# Heaterboard.net
KiCad netlist of a schematic drawn in EAGLE
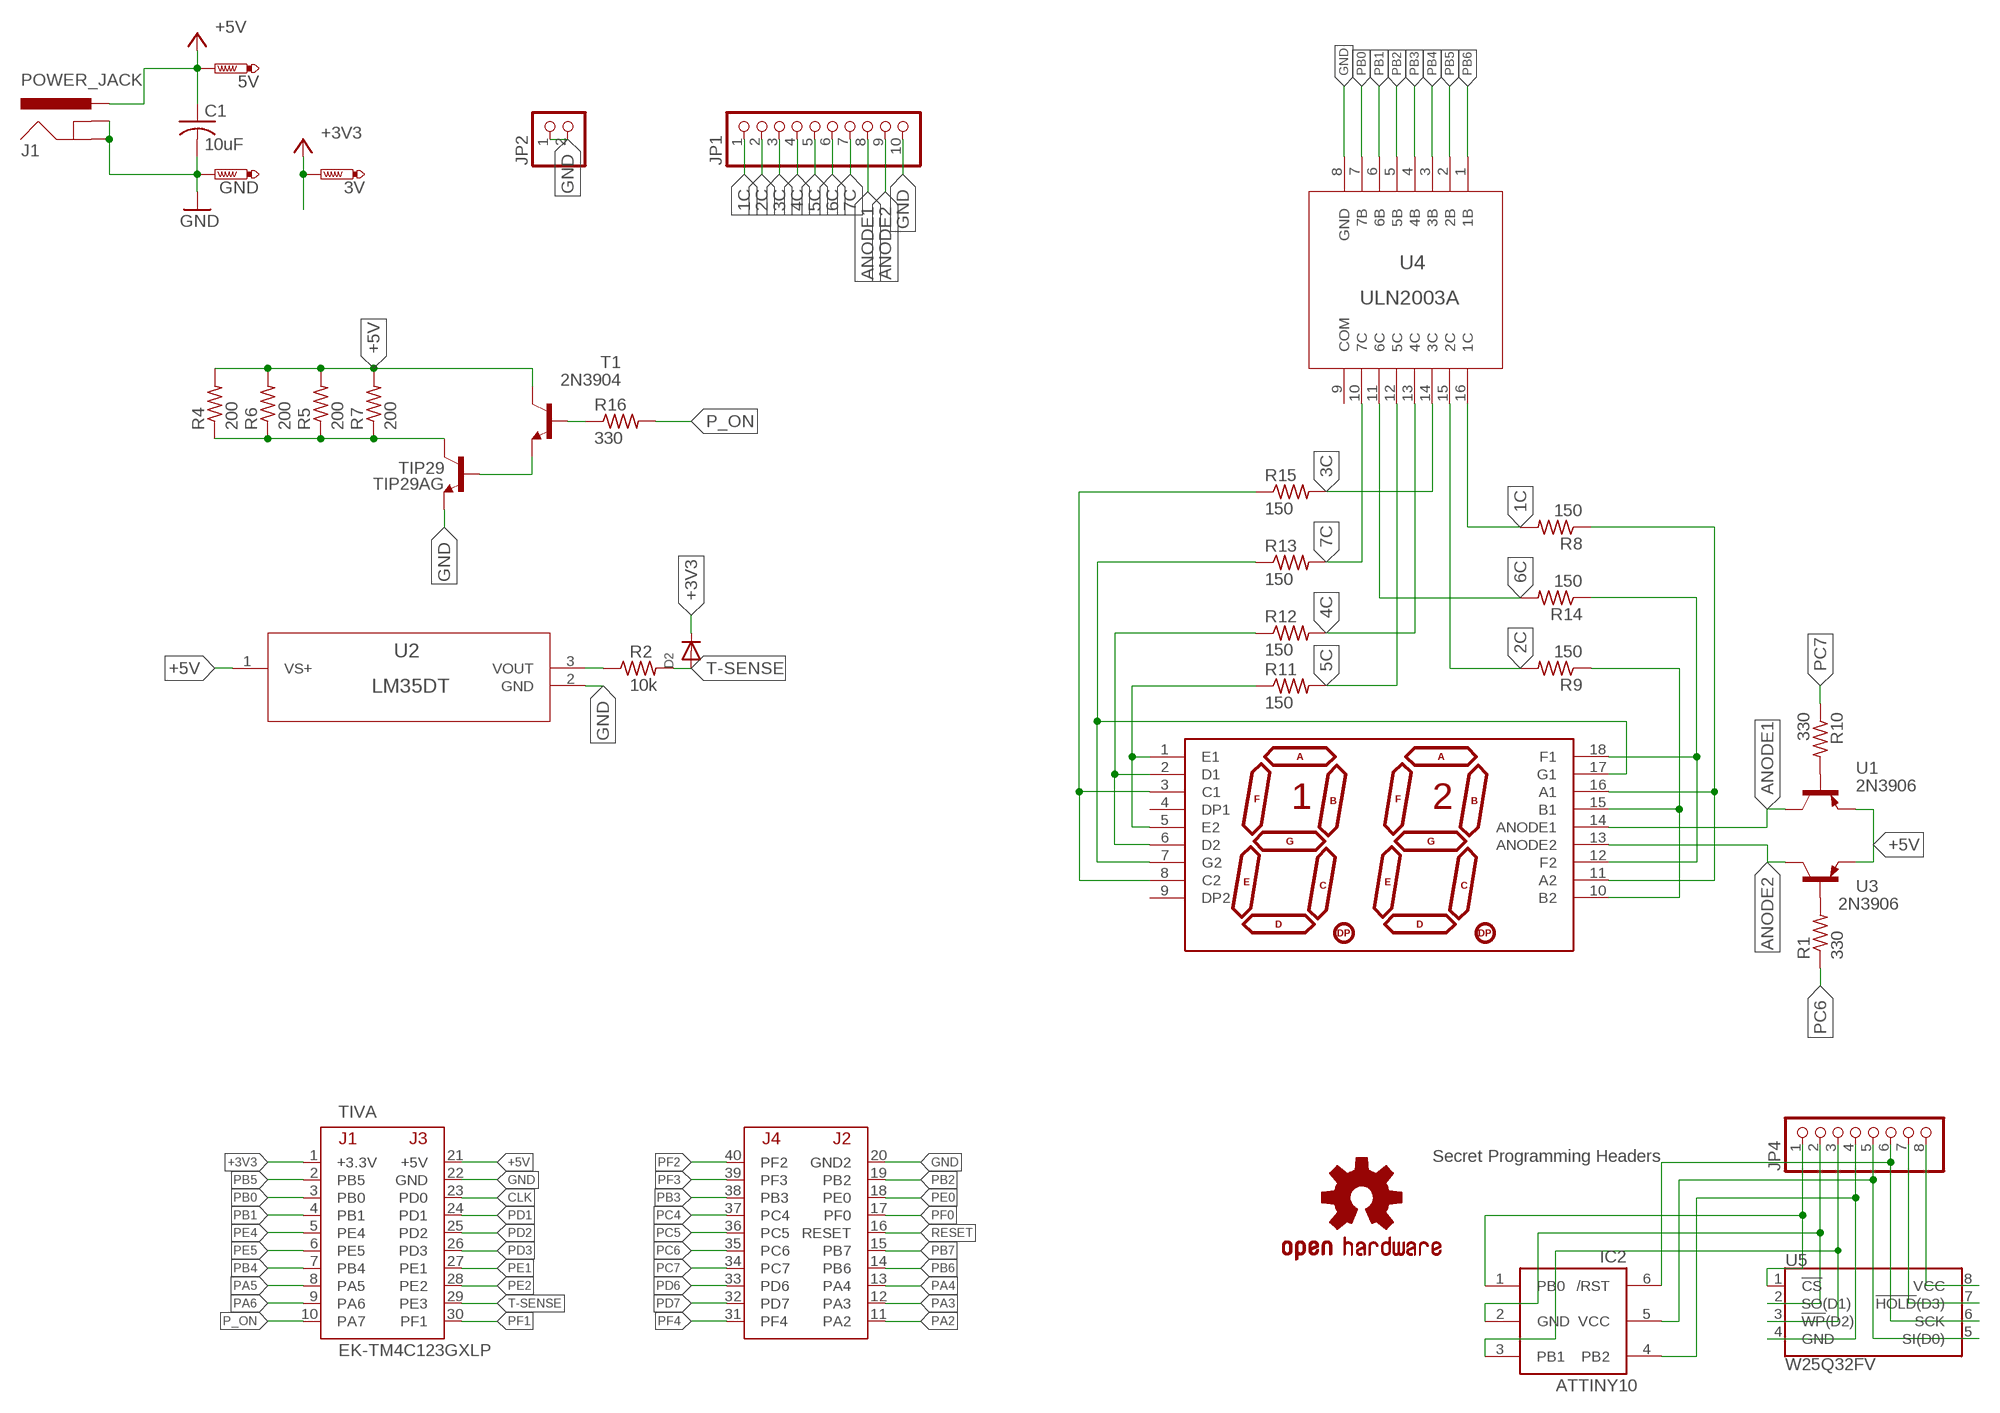
[diagram p0: schematic, sheet 1]

(export (version "E")
  (design (tool "Eeschema 10.0.6"))
  (components
    (comp (ref "3V")
      (value "PTR1PAD1-13")
      (footprint "eagle-import:P1-13")
      (libsource (lib "eagle-import") (part "PTR1PAD1-13"))
    )
    (comp (ref "5V")
      (value "PTR1PAD1-13")
      (footprint "eagle-import:P1-13")
      (libsource (lib "eagle-import") (part "PTR1PAD1-13"))
    )
    (comp (ref "7SEG")
      (value "NTE3074")
      (footprint "eagle-import:NTE3074")
      (libsource (lib "eagle-import") (part "NTE3074"))
    )
    (comp (ref "C1")
      (value "10uF")
      (footprint "eagle-import:C025-030X050")
      (libsource (lib "eagle-import") (part "C-US025-030X050"))
    )
    (comp (ref "D2")
      (value "DIODEDO-1N4148")
      (footprint "eagle-import:DO-1N4148")
      (libsource (lib "eagle-import") (part "DIODEDO-1N4148"))
    )
    (comp (ref "GND")
      (value "PTR1PAD1-13")
      (footprint "eagle-import:P1-13")
      (libsource (lib "eagle-import") (part "PTR1PAD1-13"))
    )
    (comp (ref "IC2")
      (value "ATTINY10")
      (footprint "eagle-import:SOT23-6")
      (libsource (lib "eagle-import") (part "ATTINY10"))
    )
    (comp (ref "J1")
      (value "POWER_JACK")
      (footprint "eagle-import:POWER_JACK_PTH")
      (libsource (lib "eagle-import") (part "POWER_JACK"))
    )
    (comp (ref "JP1")
      (value "PINHD-1X10/90")
      (footprint "eagle-import:1X10_90")
      (libsource (lib "eagle-import") (part "PINHD-1X10/90"))
    )
    (comp (ref "JP2")
      (value "PINHD-1X2")
      (footprint "eagle-import:1X02")
      (libsource (lib "eagle-import") (part "PINHD-1X2"))
    )
    (comp (ref "JP4")
      (value "PINHD-1X8")
      (footprint "eagle-import:1X08")
      (libsource (lib "eagle-import") (part "PINHD-1X8"))
    )
    (comp (ref "LOGO1")
      (value "OSHW-LOGOL")
      (footprint "eagle-import:OSHW-LOGO-L")
      (libsource (lib "eagle-import") (part "OSHW-LOGOL"))
    )
    (comp (ref "R1")
      (value "330")
      (footprint "eagle-import:0204_5")
      (libsource (lib "eagle-import") (part "R-US_0204/5"))
    )
    (comp (ref "R2")
      (value "10k")
      (footprint "eagle-import:0204_5")
      (libsource (lib "eagle-import") (part "R-US_0204/5"))
    )
    (comp (ref "R4")
      (value "200")
      (footprint "eagle-import:0207_10")
      (libsource (lib "eagle-import") (part "R-US_0207/10"))
    )
    (comp (ref "R5")
      (value "200")
      (footprint "eagle-import:0207_10")
      (libsource (lib "eagle-import") (part "R-US_0207/10"))
    )
    (comp (ref "R6")
      (value "200")
      (footprint "eagle-import:0207_10")
      (libsource (lib "eagle-import") (part "R-US_0207/10"))
    )
    (comp (ref "R7")
      (value "200")
      (footprint "eagle-import:0207_10")
      (libsource (lib "eagle-import") (part "R-US_0207/10"))
    )
    (comp (ref "R8")
      (value "150")
      (footprint "eagle-import:0204_5")
      (libsource (lib "eagle-import") (part "R-US_0204/5"))
    )
    (comp (ref "R9")
      (value "150")
      (footprint "eagle-import:0204_5")
      (libsource (lib "eagle-import") (part "R-US_0204/5"))
    )
    (comp (ref "R10")
      (value "330")
      (footprint "eagle-import:0204_5")
      (libsource (lib "eagle-import") (part "R-US_0204/5"))
    )
    (comp (ref "R11")
      (value "150")
      (footprint "eagle-import:0204_5")
      (libsource (lib "eagle-import") (part "R-US_0204/5"))
    )
    (comp (ref "R12")
      (value "150")
      (footprint "eagle-import:0204_5")
      (libsource (lib "eagle-import") (part "R-US_0204/5"))
    )
    (comp (ref "R13")
      (value "150")
      (footprint "eagle-import:0204_5")
      (libsource (lib "eagle-import") (part "R-US_0204/5"))
    )
    (comp (ref "R14")
      (value "150")
      (footprint "eagle-import:0204_5")
      (libsource (lib "eagle-import") (part "R-US_0204/5"))
    )
    (comp (ref "R15")
      (value "150")
      (footprint "eagle-import:0204_5")
      (libsource (lib "eagle-import") (part "R-US_0204/5"))
    )
    (comp (ref "R16")
      (value "330")
      (footprint "eagle-import:0204_5")
      (libsource (lib "eagle-import") (part "R-US_0204/5"))
    )
    (comp (ref "T1")
      (value "2N3904")
      (footprint "eagle-import:TO92")
      (libsource (lib "eagle-import") (part "2N3904"))
    )
    (comp (ref "TIP29")
      (value "TIP29AG")
      (footprint "eagle-import:TO220")
      (libsource (lib "eagle-import") (part "TIP29AG"))
    )
    (comp (ref "TIVA")
      (value "EK-TM4C123GXLP")
      (footprint "eagle-import:TM4C123LAUNCHPAD")
      (fields (field (name "MF") "Texas Instruments") (field (name "MP") "EK-TM4C123GXL"))
      (libsource (lib "eagle-import") (part "EK-TM4C123GXLP"))
    )
    (comp (ref "U1")
      (value "2N3906")
      (footprint "eagle-import:TO-92_2")
      (libsource (lib "eagle-import") (part "2N3906"))
    )
    (comp (ref "U2")
      (value "LM35DT")
      (footprint "eagle-import:TA03F")
      (libsource (lib "eagle-import") (part "LM35DT"))
    )
    (comp (ref "U3")
      (value "2N3906")
      (footprint "eagle-import:TO-92_2")
      (libsource (lib "eagle-import") (part "2N3906"))
    )
    (comp (ref "U4")
      (value "ULN2003A")
      (footprint "eagle-import:DIP-16")
      (libsource (lib "eagle-import") (part "ULN2003A"))
    )
    (comp (ref "U5")
      (value "W25Q32FV")
      (footprint "eagle-import:SOIC-8")
      (libsource (lib "eagle-import") (part "W25Q32FVSS"))
    )
  )
  (nets
    (net (code "1") (name "+3V3") (class "Default")
      (node (ref "3V") (pin "TP") (pinfunction "TP_TP") (pintype "input"))
      (node (ref "D2") (pin "C") (pinfunction "C_C") (pintype "passive"))
      (node (ref "TIVA") (pin "1") (pinfunction "+3.3V_1") (pintype "power_in"))
    )
    (net (code "2") (name "+5V") (class "Default")
      (node (ref "5V") (pin "TP") (pinfunction "TP_TP") (pintype "input"))
      (node (ref "C1") (pin "1") (pinfunction "1_1") (pintype "passive"))
      (node (ref "J1") (pin "PWR") (pinfunction "PWR_PWR") (pintype "bidirectional"))
      (node (ref "R4") (pin "2") (pinfunction "2_2") (pintype "passive"))
      (node (ref "R5") (pin "2") (pinfunction "2_2") (pintype "passive"))
      (node (ref "R6") (pin "2") (pinfunction "2_2") (pintype "passive"))
      (node (ref "R7") (pin "2") (pinfunction "2_2") (pintype "passive"))
      (node (ref "T1") (pin "1") (pinfunction "C_1") (pintype "passive"))
      (node (ref "TIVA") (pin "21") (pinfunction "+5V_21") (pintype "power_in"))
      (node (ref "U1") (pin "3") (pinfunction "E_3") (pintype "passive"))
      (node (ref "U2") (pin "1") (pinfunction "VS+_1") (pintype "input"))
      (node (ref "U3") (pin "3") (pinfunction "E_3") (pintype "passive"))
    )
    (net (code "3") (name "1C") (class "Default")
      (node (ref "JP1") (pin "1") (pinfunction "1_1") (pintype "passive"))
      (node (ref "R8") (pin "2") (pinfunction "2_2") (pintype "passive"))
      (node (ref "U4") (pin "16") (pinfunction "1C_16") (pintype "passive"))
    )
    (net (code "4") (name "2C") (class "Default")
      (node (ref "JP1") (pin "2") (pinfunction "2_2") (pintype "passive"))
      (node (ref "R9") (pin "2") (pinfunction "2_2") (pintype "passive"))
      (node (ref "U4") (pin "15") (pinfunction "2C_15") (pintype "passive"))
    )
    (net (code "5") (name "3C") (class "Default")
      (node (ref "JP1") (pin "3") (pinfunction "3_3") (pintype "passive"))
      (node (ref "R15") (pin "2") (pinfunction "2_2") (pintype "passive"))
      (node (ref "U4") (pin "14") (pinfunction "3C_14") (pintype "passive"))
    )
    (net (code "6") (name "4C") (class "Default")
      (node (ref "JP1") (pin "4") (pinfunction "4_4") (pintype "passive"))
      (node (ref "R12") (pin "2") (pinfunction "2_2") (pintype "passive"))
      (node (ref "U4") (pin "13") (pinfunction "4C_13") (pintype "passive"))
    )
    (net (code "7") (name "5C") (class "Default")
      (node (ref "JP1") (pin "5") (pinfunction "5_5") (pintype "passive"))
      (node (ref "R11") (pin "2") (pinfunction "2_2") (pintype "passive"))
      (node (ref "U4") (pin "12") (pinfunction "5C_12") (pintype "passive"))
    )
    (net (code "8") (name "6C") (class "Default")
      (node (ref "JP1") (pin "6") (pinfunction "6_6") (pintype "passive"))
      (node (ref "R14") (pin "2") (pinfunction "2_2") (pintype "passive"))
      (node (ref "U4") (pin "11") (pinfunction "6C_11") (pintype "passive"))
    )
    (net (code "9") (name "7C") (class "Default")
      (node (ref "JP1") (pin "7") (pinfunction "7_7") (pintype "passive"))
      (node (ref "R13") (pin "2") (pinfunction "2_2") (pintype "passive"))
      (node (ref "U4") (pin "10") (pinfunction "7C_10") (pintype "passive"))
    )
    (net (code "10") (name "ANODE1") (class "Default")
      (node (ref "7SEG") (pin "14") (pinfunction "ANODE1_14") (pintype "bidirectional"))
      (node (ref "JP1") (pin "8") (pinfunction "8_8") (pintype "passive"))
      (node (ref "U1") (pin "1") (pinfunction "C_1") (pintype "passive"))
    )
    (net (code "11") (name "ANODE2") (class "Default")
      (node (ref "7SEG") (pin "13") (pinfunction "ANODE2_13") (pintype "bidirectional"))
      (node (ref "JP1") (pin "9") (pinfunction "9_9") (pintype "passive"))
      (node (ref "U3") (pin "1") (pinfunction "C_1") (pintype "passive"))
    )
    (net (code "12") (name "CLK") (class "Default")
      (node (ref "TIVA") (pin "23") (pinfunction "PD0_23") (pintype "bidirectional"))
    )
    (net (code "13") (name "GND") (class "Default")
      (node (ref "C1") (pin "2") (pinfunction "2_2") (pintype "passive"))
      (node (ref "GND") (pin "TP") (pinfunction "TP_TP") (pintype "input"))
      (node (ref "J1") (pin "GND") (pinfunction "GND_GND") (pintype "bidirectional"))
      (node (ref "J1") (pin "GNDBREAK") (pinfunction "GNDBREAK_GNDBREAK") (pintype "bidirectional"))
      (node (ref "JP1") (pin "10") (pinfunction "10_10") (pintype "passive"))
      (node (ref "JP2") (pin "1") (pinfunction "1_1") (pintype "passive"))
      (node (ref "JP2") (pin "2") (pinfunction "2_2") (pintype "passive"))
      (node (ref "TIP29") (pin "3") (pinfunction "E_3") (pintype "passive"))
      (node (ref "TIVA") (pin "20") (pinfunction "GND2_20") (pintype "power_in"))
      (node (ref "TIVA") (pin "22") (pinfunction "GND_22") (pintype "power_in"))
      (node (ref "U2") (pin "2") (pinfunction "GND_2") (pintype "passive"))
      (node (ref "U4") (pin "8") (pinfunction "GND_8") (pintype "passive"))
    )
    (net (code "14") (name "Net-(7SEG-A1)") (class "Default")
      (node (ref "7SEG") (pin "11") (pinfunction "A2_11") (pintype "bidirectional"))
      (node (ref "7SEG") (pin "16") (pinfunction "A1_16") (pintype "bidirectional"))
      (node (ref "R8") (pin "1") (pinfunction "1_1") (pintype "passive"))
    )
    (net (code "15") (name "Net-(7SEG-B1)") (class "Default")
      (node (ref "7SEG") (pin "10") (pinfunction "B2_10") (pintype "bidirectional"))
      (node (ref "7SEG") (pin "15") (pinfunction "B1_15") (pintype "bidirectional"))
      (node (ref "R9") (pin "1") (pinfunction "1_1") (pintype "passive"))
    )
    (net (code "16") (name "Net-(7SEG-C1)") (class "Default")
      (node (ref "7SEG") (pin "3") (pinfunction "C1_3") (pintype "bidirectional"))
      (node (ref "7SEG") (pin "8") (pinfunction "C2_8") (pintype "bidirectional"))
      (node (ref "R15") (pin "1") (pinfunction "1_1") (pintype "passive"))
    )
    (net (code "17") (name "Net-(7SEG-D1)") (class "Default")
      (node (ref "7SEG") (pin "2") (pinfunction "D1_2") (pintype "bidirectional"))
      (node (ref "7SEG") (pin "6") (pinfunction "D2_6") (pintype "bidirectional"))
      (node (ref "R12") (pin "1") (pinfunction "1_1") (pintype "passive"))
    )
    (net (code "18") (name "Net-(7SEG-E1)") (class "Default")
      (node (ref "7SEG") (pin "1") (pinfunction "E1_1") (pintype "bidirectional"))
      (node (ref "7SEG") (pin "5") (pinfunction "E2_5") (pintype "bidirectional"))
      (node (ref "R11") (pin "1") (pinfunction "1_1") (pintype "passive"))
    )
    (net (code "19") (name "Net-(7SEG-F1)") (class "Default")
      (node (ref "7SEG") (pin "12") (pinfunction "F2_12") (pintype "bidirectional"))
      (node (ref "7SEG") (pin "18") (pinfunction "F1_18") (pintype "bidirectional"))
      (node (ref "R14") (pin "1") (pinfunction "1_1") (pintype "passive"))
    )
    (net (code "20") (name "Net-(7SEG-G1)") (class "Default")
      (node (ref "7SEG") (pin "17") (pinfunction "G1_17") (pintype "bidirectional"))
      (node (ref "7SEG") (pin "7") (pinfunction "G2_7") (pintype "bidirectional"))
      (node (ref "R13") (pin "1") (pinfunction "1_1") (pintype "passive"))
    )
    (net (code "21") (name "Net-(IC2-GND)") (class "Default")
      (node (ref "IC2") (pin "2") (pinfunction "GND_2") (pintype "power_in"))
      (node (ref "JP4") (pin "2") (pinfunction "2_2") (pintype "passive"))
      (node (ref "U5") (pin "2") (pinfunction "SO(D1)_2") (pintype "bidirectional"))
    )
    (net (code "22") (name "Net-(IC2-PB0)") (class "Default")
      (node (ref "IC2") (pin "1") (pinfunction "PB0_1") (pintype "bidirectional"))
      (node (ref "JP4") (pin "1") (pinfunction "1_1") (pintype "passive"))
      (node (ref "U5") (pin "1") (pinfunction "~{CS}_1") (pintype "bidirectional"))
    )
    (net (code "23") (name "Net-(IC2-PB1)") (class "Default")
      (node (ref "IC2") (pin "3") (pinfunction "PB1_3") (pintype "bidirectional"))
      (node (ref "JP4") (pin "3") (pinfunction "3_3") (pintype "passive"))
      (node (ref "U5") (pin "3") (pinfunction "~{WP}(D2)_3") (pintype "bidirectional"))
    )
    (net (code "24") (name "Net-(IC2-PB2)") (class "Default")
      (node (ref "IC2") (pin "4") (pinfunction "PB2_4") (pintype "bidirectional"))
      (node (ref "JP4") (pin "4") (pinfunction "4_4") (pintype "passive"))
      (node (ref "U5") (pin "4") (pinfunction "GND_4") (pintype "bidirectional"))
    )
    (net (code "25") (name "Net-(IC2-VCC)") (class "Default")
      (node (ref "IC2") (pin "5") (pinfunction "VCC_5") (pintype "power_in"))
      (node (ref "JP4") (pin "5") (pinfunction "5_5") (pintype "passive"))
      (node (ref "U5") (pin "5") (pinfunction "SI(D0)_5") (pintype "bidirectional"))
    )
    (net (code "26") (name "Net-(IC2-{slash}RST)") (class "Default")
      (node (ref "IC2") (pin "6") (pinfunction "/RST_6") (pintype "bidirectional"))
      (node (ref "JP4") (pin "6") (pinfunction "6_6") (pintype "passive"))
      (node (ref "U5") (pin "6") (pinfunction "SCK_6") (pintype "bidirectional"))
    )
    (net (code "27") (name "Net-(T1-B)") (class "Default")
      (node (ref "R16") (pin "1") (pinfunction "1_1") (pintype "passive"))
      (node (ref "T1") (pin "2") (pinfunction "B_2") (pintype "passive"))
    )
    (net (code "28") (name "Net-(T1-E)") (class "Default")
      (node (ref "T1") (pin "3") (pinfunction "E_3") (pintype "passive"))
      (node (ref "TIP29") (pin "1") (pinfunction "B_1") (pintype "passive"))
    )
    (net (code "29") (name "Net-(TIP29-C)") (class "Default")
      (node (ref "R4") (pin "1") (pinfunction "1_1") (pintype "passive"))
      (node (ref "R5") (pin "1") (pinfunction "1_1") (pintype "passive"))
      (node (ref "R6") (pin "1") (pinfunction "1_1") (pintype "passive"))
      (node (ref "R7") (pin "1") (pinfunction "1_1") (pintype "passive"))
      (node (ref "TIP29") (pin "2") (pinfunction "C_2") (pintype "passive"))
    )
    (net (code "30") (name "Net-(U1-B)") (class "Default")
      (node (ref "R10") (pin "2") (pinfunction "2_2") (pintype "passive"))
      (node (ref "U1") (pin "2") (pinfunction "B_2") (pintype "passive"))
    )
    (net (code "31") (name "Net-(U2-VOUT)") (class "Default")
      (node (ref "R2") (pin "1") (pinfunction "1_1") (pintype "passive"))
      (node (ref "U2") (pin "3") (pinfunction "VOUT_3") (pintype "output"))
    )
    (net (code "32") (name "Net-(U3-B)") (class "Default")
      (node (ref "R1") (pin "2") (pinfunction "2_2") (pintype "passive"))
      (node (ref "U3") (pin "2") (pinfunction "B_2") (pintype "passive"))
    )
    (net (code "33") (name "Net-(U5-VCC)") (class "Default")
      (node (ref "JP4") (pin "8") (pinfunction "8_8") (pintype "passive"))
      (node (ref "U5") (pin "8") (pinfunction "VCC_8") (pintype "bidirectional"))
    )
    (net (code "34") (name "Net-(U5-~{HOLD}(D3))") (class "Default")
      (node (ref "JP4") (pin "7") (pinfunction "7_7") (pintype "passive"))
      (node (ref "U5") (pin "7") (pinfunction "~{HOLD}(D3)_7") (pintype "bidirectional"))
    )
    (net (code "35") (name "PA2") (class "Default")
      (node (ref "TIVA") (pin "11") (pinfunction "PA2_11") (pintype "bidirectional"))
    )
    (net (code "36") (name "PA3") (class "Default")
      (node (ref "TIVA") (pin "12") (pinfunction "PA3_12") (pintype "bidirectional"))
    )
    (net (code "37") (name "PA4") (class "Default")
      (node (ref "TIVA") (pin "13") (pinfunction "PA4_13") (pintype "bidirectional"))
    )
    (net (code "38") (name "PA5") (class "Default")
      (node (ref "TIVA") (pin "8") (pinfunction "PA5_8") (pintype "bidirectional"))
    )
    (net (code "39") (name "PA6") (class "Default")
      (node (ref "TIVA") (pin "9") (pinfunction "PA6_9") (pintype "bidirectional"))
    )
    (net (code "40") (name "PB0") (class "Default")
      (node (ref "TIVA") (pin "3") (pinfunction "PB0_3") (pintype "bidirectional"))
      (node (ref "U4") (pin "7") (pinfunction "7B_7") (pintype "input"))
    )
    (net (code "41") (name "PB1") (class "Default")
      (node (ref "TIVA") (pin "4") (pinfunction "PB1_4") (pintype "bidirectional"))
      (node (ref "U4") (pin "6") (pinfunction "6B_6") (pintype "input"))
    )
    (net (code "42") (name "PB2") (class "Default")
      (node (ref "TIVA") (pin "19") (pinfunction "PB2_19") (pintype "bidirectional"))
      (node (ref "U4") (pin "5") (pinfunction "5B_5") (pintype "input"))
    )
    (net (code "43") (name "PB3") (class "Default")
      (node (ref "TIVA") (pin "38") (pinfunction "PB3_38") (pintype "bidirectional"))
      (node (ref "U4") (pin "4") (pinfunction "4B_4") (pintype "input"))
    )
    (net (code "44") (name "PB4") (class "Default")
      (node (ref "TIVA") (pin "7") (pinfunction "PB4_7") (pintype "bidirectional"))
      (node (ref "U4") (pin "3") (pinfunction "3B_3") (pintype "input"))
    )
    (net (code "45") (name "PB5") (class "Default")
      (node (ref "TIVA") (pin "2") (pinfunction "PB5_2") (pintype "bidirectional"))
      (node (ref "U4") (pin "2") (pinfunction "2B_2") (pintype "input"))
    )
    (net (code "46") (name "PB6") (class "Default")
      (node (ref "TIVA") (pin "14") (pinfunction "PB6_14") (pintype "bidirectional"))
      (node (ref "U4") (pin "1") (pinfunction "1B_1") (pintype "input"))
    )
    (net (code "47") (name "PB7") (class "Default")
      (node (ref "TIVA") (pin "15") (pinfunction "PB7_15") (pintype "bidirectional"))
    )
    (net (code "48") (name "PC4") (class "Default")
      (node (ref "TIVA") (pin "37") (pinfunction "PC4_37") (pintype "bidirectional"))
    )
    (net (code "49") (name "PC5") (class "Default")
      (node (ref "TIVA") (pin "36") (pinfunction "PC5_36") (pintype "bidirectional"))
    )
    (net (code "50") (name "PC6") (class "Default")
      (node (ref "R1") (pin "1") (pinfunction "1_1") (pintype "passive"))
      (node (ref "TIVA") (pin "35") (pinfunction "PC6_35") (pintype "bidirectional"))
    )
    (net (code "51") (name "PC7") (class "Default")
      (node (ref "R10") (pin "1") (pinfunction "1_1") (pintype "passive"))
      (node (ref "TIVA") (pin "34") (pinfunction "PC7_34") (pintype "bidirectional"))
    )
    (net (code "52") (name "PD1") (class "Default")
      (node (ref "TIVA") (pin "24") (pinfunction "PD1_24") (pintype "bidirectional"))
    )
    (net (code "53") (name "PD2") (class "Default")
      (node (ref "TIVA") (pin "25") (pinfunction "PD2_25") (pintype "bidirectional"))
    )
    (net (code "54") (name "PD3") (class "Default")
      (node (ref "TIVA") (pin "26") (pinfunction "PD3_26") (pintype "bidirectional"))
    )
    (net (code "55") (name "PD6") (class "Default")
      (node (ref "TIVA") (pin "33") (pinfunction "PD6_33") (pintype "bidirectional"))
    )
    (net (code "56") (name "PD7") (class "Default")
      (node (ref "TIVA") (pin "32") (pinfunction "PD7_32") (pintype "bidirectional"))
    )
    (net (code "57") (name "PE0") (class "Default")
      (node (ref "TIVA") (pin "18") (pinfunction "PE0_18") (pintype "bidirectional"))
    )
    (net (code "58") (name "PE1") (class "Default")
      (node (ref "TIVA") (pin "27") (pinfunction "PE1_27") (pintype "bidirectional"))
    )
    (net (code "59") (name "PE2") (class "Default")
      (node (ref "TIVA") (pin "28") (pinfunction "PE2_28") (pintype "bidirectional"))
    )
    (net (code "60") (name "PE4") (class "Default")
      (node (ref "TIVA") (pin "5") (pinfunction "PE4_5") (pintype "bidirectional"))
    )
    (net (code "61") (name "PE5") (class "Default")
      (node (ref "TIVA") (pin "6") (pinfunction "PE5_6") (pintype "bidirectional"))
    )
    (net (code "62") (name "PF0") (class "Default")
      (node (ref "TIVA") (pin "17") (pinfunction "PF0_17") (pintype "bidirectional"))
    )
    (net (code "63") (name "PF1") (class "Default")
      (node (ref "TIVA") (pin "30") (pinfunction "PF1_30") (pintype "bidirectional"))
    )
    (net (code "64") (name "PF2") (class "Default")
      (node (ref "TIVA") (pin "40") (pinfunction "PF2_40") (pintype "bidirectional"))
    )
    (net (code "65") (name "PF3") (class "Default")
      (node (ref "TIVA") (pin "39") (pinfunction "PF3_39") (pintype "bidirectional"))
    )
    (net (code "66") (name "PF4") (class "Default")
      (node (ref "TIVA") (pin "31") (pinfunction "PF4_31") (pintype "bidirectional"))
    )
    (net (code "67") (name "P_ON") (class "Default")
      (node (ref "R16") (pin "2") (pinfunction "2_2") (pintype "passive"))
      (node (ref "TIVA") (pin "10") (pinfunction "PA7_10") (pintype "bidirectional"))
    )
    (net (code "68") (name "RESET") (class "Default")
      (node (ref "TIVA") (pin "16") (pinfunction "RESET_16") (pintype "input"))
    )
    (net (code "69") (name "T-SENSE") (class "Default")
      (node (ref "D2") (pin "A") (pinfunction "A_A") (pintype "passive"))
      (node (ref "R2") (pin "2") (pinfunction "2_2") (pintype "passive"))
      (node (ref "TIVA") (pin "29") (pinfunction "PE3_29") (pintype "bidirectional"))
    )
    (net (code "70") (name "unconnected-(7SEG-DP1-Pad4)") (class "Default")
      (node (ref "7SEG") (pin "4") (pinfunction "DP1_4") (pintype "bidirectional"))
    )
    (net (code "71") (name "unconnected-(7SEG-DP2-Pad9)") (class "Default")
      (node (ref "7SEG") (pin "9") (pinfunction "DP2_9") (pintype "bidirectional"))
    )
    (net (code "72") (name "unconnected-(U4-COM-Pad9)") (class "Default")
      (node (ref "U4") (pin "9") (pinfunction "COM_9") (pintype "passive"))
    )
  )
)
